# Telemetria.net
KiCad netlist of a schematic drawn in Altium Designer
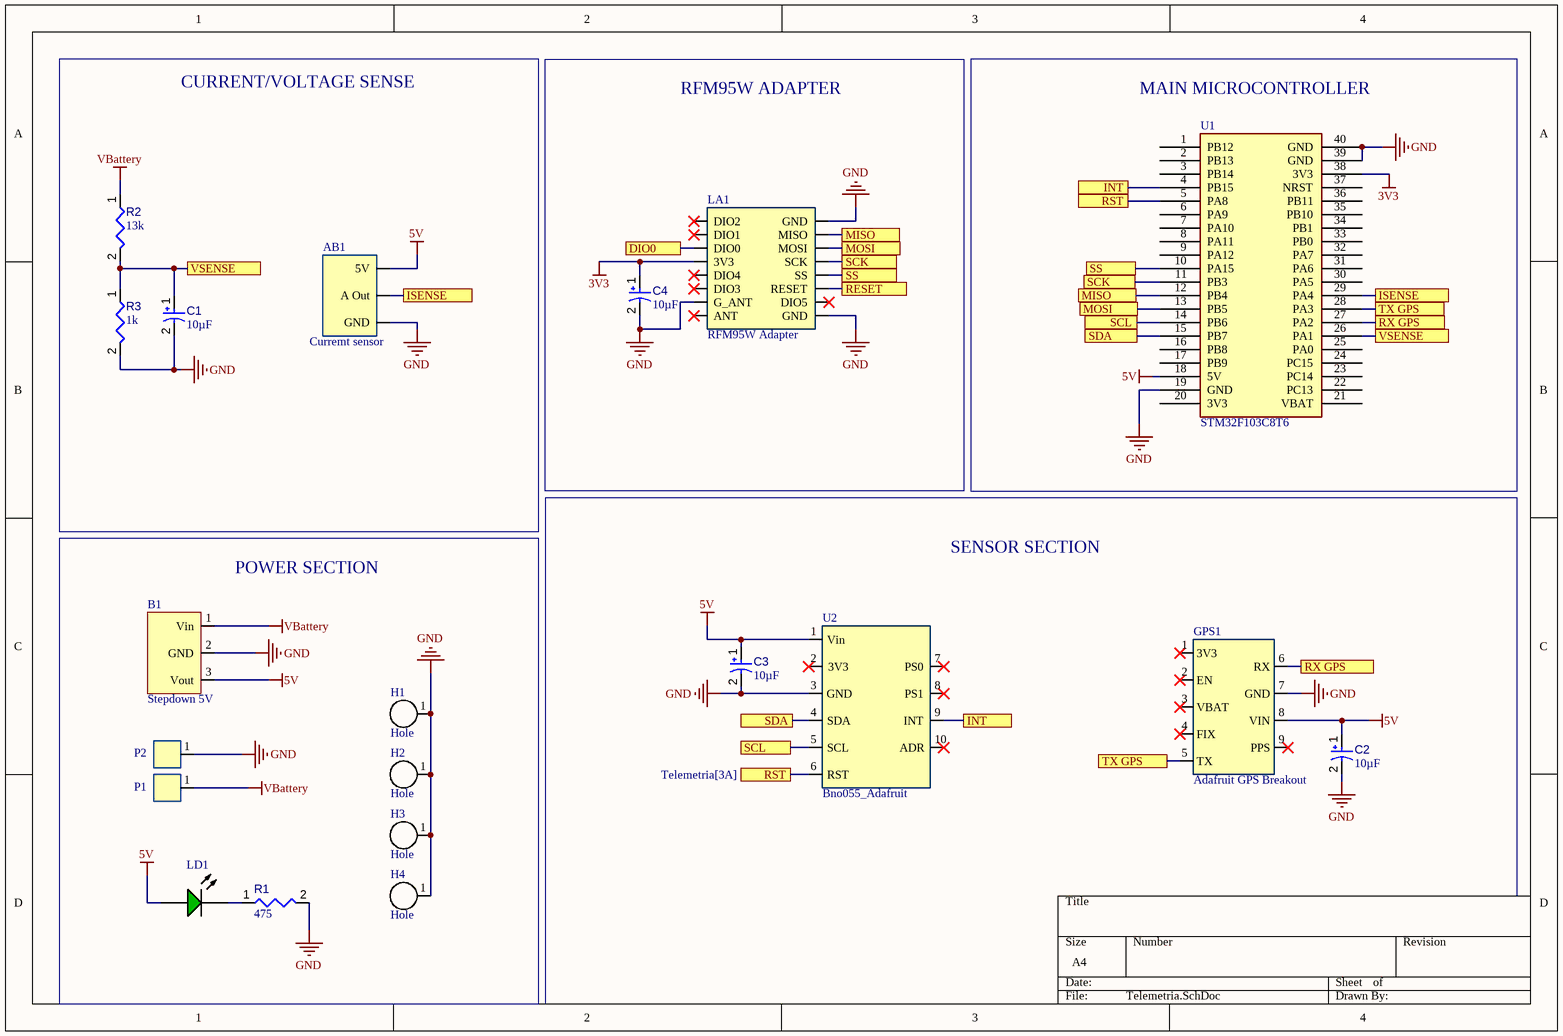
[diagram p0: Telemetria.SchDoc]

(export (version "E")
  (design (tool "Eeschema 10.0.6"))
  (components
    (comp (ref "AB1")
      (value "Curremt sensor")
      (footprint "ACS712 Board")
      (description "ACS712 HAll effect based current sensor")
      (libsource (lib "Bno055_Adafruit") (part "ACS712 Board"))
    )
    (comp (ref "B1")
      (value "Stepdown 5V")
      (footprint "StepDown 5V")
      (description "Buck converter DC-DC 5v Mornsun - K78U05-500R3")
      (libsource (lib "Bno055_Adafruit") (part "Stepdown 5V"))
    )
    (comp (ref "C1")
      (value "10µF")
      (footprint "CAPPR55-200-1100X500X1200")
      (description "Aluminum Electrolytic Capacitor, 10 uF, +/- 20%, 50 V, -40 to 85 degC, 2-Pin THD, RoHS, Bulk")
      (fields (field (name "MANUFACTURER") "Panasonic") (field (name "TOLERANCE") "20%"))
      (libsource (lib "Elyos SEM") (part "CAP-P-2"))
    )
    (comp (ref "C2")
      (value "10µF")
      (footprint "CAPPR55-200-1100X500X1200")
      (description "Aluminum Electrolytic Capacitor, 10 uF, +/- 20%, 50 V, -40 to 85 degC, 2-Pin THD, RoHS, Bulk")
      (fields (field (name "MANUFACTURER") "Panasonic") (field (name "TOLERANCE") "20%"))
      (libsource (lib "Elyos SEM") (part "CAP-P-2"))
    )
    (comp (ref "C3")
      (value "10µF")
      (footprint "CAPPR55-200-1100X500X1200")
      (description "Aluminum Electrolytic Capacitor, 10 uF, +/- 20%, 50 V, -40 to 85 degC, 2-Pin THD, RoHS, Bulk")
      (fields (field (name "MANUFACTURER") "Panasonic") (field (name "TOLERANCE") "20%"))
      (libsource (lib "Elyos SEM") (part "CAP-P-2"))
    )
    (comp (ref "C4")
      (value "10µF")
      (footprint "CAPPR55-200-1100X500X1200")
      (description "Aluminum Electrolytic Capacitor, 10 uF, +/- 20%, 50 V, -40 to 85 degC, 2-Pin THD, RoHS, Bulk")
      (fields (field (name "MANUFACTURER") "Panasonic") (field (name "TOLERANCE") "20%"))
      (libsource (lib "Elyos SEM") (part "CAP-P-2"))
    )
    (comp (ref "GPS1")
      (value "Adafruit GPS Breakout")
      (footprint "Adafruit GPS breakout")
      (description "Adafruit GPS Breakout DIP Board")
      (libsource (lib "Bno055_Adafruit") (part "Adafruit GPS"))
    )
    (comp (ref "H1")
      (value "Hole")
      (footprint "Hole")
      (description "Circular hole for attaching PCB")
      (libsource (lib "Bno055_Adafruit") (part "Hole"))
    )
    (comp (ref "H2")
      (value "Hole")
      (footprint "Hole")
      (description "Circular hole for attaching PCB")
      (libsource (lib "Bno055_Adafruit") (part "Hole"))
    )
    (comp (ref "H3")
      (value "Hole")
      (footprint "Hole")
      (description "Circular hole for attaching PCB")
      (libsource (lib "Bno055_Adafruit") (part "Hole"))
    )
    (comp (ref "H4")
      (value "Hole")
      (footprint "Hole")
      (description "Circular hole for attaching PCB")
      (libsource (lib "Bno055_Adafruit") (part "Hole"))
    )
    (comp (ref "LA1")
      (value "RFM95W Adapter")
      (footprint "Lora Adapter")
      (libsource (lib "Bno055_Adafruit") (part "Lora Adapter"))
    )
    (comp (ref "LD1")
      (value "304090040")
      (footprint "LED-2P-2.28-3MM")
      (description "Green LED, 80 mW, 20 mA, -25 to 85 degC, 2-Pin THD")
      (fields (field (name "MANUFACTURER") "Shenzhen CGX"))
      (libsource (lib "Elyos SEM") (part "LED-GREEN-AK-2"))
    )
    (comp (ref "P1")
      (value "High power pad")
      (footprint "HIGH_POWER_PAD")
      (description "High power pads (7.5 x 15 mm)")
      (libsource (lib "Bno055_Adafruit") (part "HIGH_POWER_PAD"))
    )
    (comp (ref "P2")
      (value "High power pad")
      (footprint "HIGH_POWER_PAD")
      (description "High power pads (7.5 x 15 mm)")
      (libsource (lib "Bno055_Adafruit") (part "HIGH_POWER_PAD"))
    )
    (comp (ref "R1")
      (value "475")
      (footprint "RESA60-630X240")
      (description "Axial Resistor, 475 Ohm, +/- 1%, 0.25 W, -55 to 155 degC, 2-Pin THD, RoHS, Bulk")
      (fields (field (name "MANUFACTURER") "Yageo") (field (name "TOLERANCE") "1%"))
      (libsource (lib "Elyos SEM") (part "RES-2"))
    )
    (comp (ref "R2")
      (value "13k")
      (footprint "RESA60-630X240")
      (description "Axial Resistor, 1 KOhm, +/- 1%, 250 mW, -55 to 155 degC, 2-Pin THD, RoHS, Bulk")
      (fields (field (name "TOLERANCE") "1%") (field (name "POWER") "250mW"))
      (libsource (lib "Elyos SEM") (part "RES-2"))
    )
    (comp (ref "R3")
      (value "1k")
      (footprint "RESA60-630X240")
      (description "Axial Resistor, 1 KOhm, +/- 1%, 250 mW, -55 to 155 degC, 2-Pin THD, RoHS, Bulk")
      (fields (field (name "TOLERANCE") "1%") (field (name "POWER") "250mW"))
      (libsource (lib "Elyos SEM") (part "RES-2"))
    )
    (comp (ref "U1")
      (value "STM32F103C8T6")
      (footprint "Stm32 BluePill")
      (description "Designed By @Alixahedi")
      (libsource (lib "Stm32 Blue Pill") (part "BluePill"))
    )
    (comp (ref "U2")
      (value "Bno055_Adafruit")
      (footprint "Bno055_Adafruit")
      (description "Adafruit IMU breakout part 2472 based on Bosch BNO055 IC")
      (libsource (lib "Bno055_Adafruit") (part "Bno055_Adafruit"))
    )
  )
  (nets
    (net (code "1") (name "/DIO0") (class "Default")
      (node (ref "LA1") (pin "3") (pinfunction "DIO0_3") (pintype "passive"))
    )
    (net (code "2") (name "/INT") (class "Default")
      (node (ref "U1") (pin "4") (pinfunction "PB15_4") (pintype "passive"))
      (node (ref "U2") (pin "9") (pinfunction "INT_9") (pintype "passive"))
    )
    (net (code "3") (name "/ISENSE") (class "Default")
      (node (ref "AB1") (pin "2") (pinfunction "A_Out_2") (pintype "passive"))
      (node (ref "U1") (pin "29") (pinfunction "PA4_29") (pintype "passive"))
    )
    (net (code "4") (name "/MISO") (class "Default")
      (node (ref "LA1") (pin "10") (pinfunction "MISO_10") (pintype "passive"))
      (node (ref "U1") (pin "12") (pinfunction "PB4_12") (pintype "passive"))
    )
    (net (code "5") (name "/MOSI") (class "Default")
      (node (ref "LA1") (pin "11") (pinfunction "MOSI_11") (pintype "passive"))
      (node (ref "U1") (pin "13") (pinfunction "PB5_13") (pintype "passive"))
    )
    (net (code "6") (name "/RESET") (class "Default")
      (node (ref "LA1") (pin "14") (pinfunction "RESET_14") (pintype "passive"))
    )
    (net (code "7") (name "/RST") (class "Default")
      (node (ref "U1") (pin "5") (pinfunction "PA8_5") (pintype "passive"))
      (node (ref "U2") (pin "6") (pinfunction "RST_6") (pintype "passive"))
    )
    (net (code "8") (name "/RX GPS") (class "Default")
      (node (ref "GPS1") (pin "6") (pinfunction "RX_6") (pintype "passive"))
      (node (ref "U1") (pin "27") (pinfunction "PA2_27") (pintype "passive"))
    )
    (net (code "9") (name "/SCK") (class "Default")
      (node (ref "LA1") (pin "12") (pinfunction "SCK_12") (pintype "passive"))
      (node (ref "U1") (pin "11") (pinfunction "PB3_11") (pintype "passive"))
    )
    (net (code "10") (name "/SCL") (class "Default")
      (node (ref "U1") (pin "14") (pinfunction "PB6_14") (pintype "passive"))
      (node (ref "U2") (pin "5") (pinfunction "SCL_5") (pintype "passive"))
    )
    (net (code "11") (name "/SDA") (class "Default")
      (node (ref "U1") (pin "15") (pinfunction "PB7_15") (pintype "passive"))
      (node (ref "U2") (pin "4") (pinfunction "SDA_4") (pintype "passive"))
    )
    (net (code "12") (name "/SS") (class "Default")
      (node (ref "LA1") (pin "13") (pinfunction "SS_13") (pintype "passive"))
      (node (ref "U1") (pin "10") (pinfunction "PA15_10") (pintype "passive"))
    )
    (net (code "13") (name "/TX GPS") (class "Default")
      (node (ref "GPS1") (pin "5") (pinfunction "TX_5") (pintype "passive"))
      (node (ref "U1") (pin "28") (pinfunction "PA3_28") (pintype "passive"))
    )
    (net (code "14") (name "/VSENSE") (class "Default")
      (node (ref "C1") (pin "1") (pinfunction "1_1") (pintype "passive"))
      (node (ref "R2") (pin "2") (pinfunction "2_2") (pintype "passive"))
      (node (ref "R3") (pin "1") (pinfunction "1_1") (pintype "passive"))
      (node (ref "U1") (pin "26") (pinfunction "PA1_26") (pintype "passive"))
    )
    (net (code "15") (name "3V3") (class "Default")
      (node (ref "C4") (pin "1") (pinfunction "1_1") (pintype "passive"))
      (node (ref "LA1") (pin "4") (pinfunction "3V3_4") (pintype "power_in"))
      (node (ref "U1") (pin "38") (pinfunction "3V3_38") (pintype "passive"))
    )
    (net (code "16") (name "5V") (class "Default")
      (node (ref "AB1") (pin "3") (pinfunction "5V_3") (pintype "passive"))
      (node (ref "B1") (pin "3") (pinfunction "Vout_3") (pintype "passive"))
      (node (ref "C2") (pin "1") (pinfunction "1_1") (pintype "passive"))
      (node (ref "C3") (pin "1") (pinfunction "1_1") (pintype "passive"))
      (node (ref "GPS1") (pin "8") (pinfunction "VIN_8") (pintype "passive"))
      (node (ref "LD1") (pin "1") (pinfunction "A_1") (pintype "passive"))
      (node (ref "U1") (pin "18") (pinfunction "5V_18") (pintype "passive"))
      (node (ref "U2") (pin "1") (pinfunction "__Vin_1") (pintype "passive"))
    )
    (net (code "17") (name "GND") (class "Default")
      (node (ref "AB1") (pin "1") (pinfunction "GND_1") (pintype "passive"))
      (node (ref "B1") (pin "2") (pinfunction "GND_2") (pintype "passive"))
      (node (ref "C1") (pin "2") (pinfunction "2_2") (pintype "passive"))
      (node (ref "C2") (pin "2") (pinfunction "2_2") (pintype "passive"))
      (node (ref "C3") (pin "2") (pinfunction "2_2") (pintype "passive"))
      (node (ref "C4") (pin "2") (pinfunction "2_2") (pintype "passive"))
      (node (ref "GPS1") (pin "7") (pinfunction "GND_7") (pintype "passive"))
      (node (ref "H1") (pin "1") (pinfunction "GND_1") (pintype "passive"))
      (node (ref "H2") (pin "1") (pinfunction "GND_1") (pintype "passive"))
      (node (ref "H3") (pin "1") (pinfunction "GND_1") (pintype "passive"))
      (node (ref "H4") (pin "1") (pinfunction "GND_1") (pintype "passive"))
      (node (ref "LA1") (pin "16") (pinfunction "GND_16") (pintype "passive"))
      (node (ref "LA1") (pin "7") (pinfunction "G_ANT_7") (pintype "passive"))
      (node (ref "LA1") (pin "9") (pinfunction "GND_9") (pintype "passive"))
      (node (ref "P2") (pin "1") (pinfunction "PAD_1") (pintype "passive"))
      (node (ref "R1") (pin "2") (pinfunction "2_2") (pintype "passive"))
      (node (ref "R3") (pin "2") (pinfunction "2_2") (pintype "passive"))
      (node (ref "U1") (pin "19") (pinfunction "GND_19") (pintype "passive"))
      (node (ref "U1") (pin "39") (pinfunction "GND_39") (pintype "passive"))
      (node (ref "U1") (pin "40") (pinfunction "GND_40") (pintype "passive"))
      (node (ref "U2") (pin "3") (pinfunction "GND_3") (pintype "passive"))
    )
    (net (code "18") (name "Net-(LD1-K)") (class "Default")
      (node (ref "LD1") (pin "2") (pinfunction "K_2") (pintype "passive"))
      (node (ref "R1") (pin "1") (pinfunction "1_1") (pintype "passive"))
    )
    (net (code "19") (name "VBattery") (class "Default")
      (node (ref "B1") (pin "1") (pinfunction "Vin_1") (pintype "passive"))
      (node (ref "P1") (pin "1") (pinfunction "PAD_1") (pintype "passive"))
      (node (ref "R2") (pin "1") (pinfunction "1_1") (pintype "passive"))
    )
    (net (code "20") (name "unconnected-(GPS1-3V3-Pad1)") (class "Default")
      (node (ref "GPS1") (pin "1") (pinfunction "3V3_1") (pintype "passive+no_connect"))
    )
    (net (code "21") (name "unconnected-(GPS1-EN-Pad2)") (class "Default")
      (node (ref "GPS1") (pin "2") (pinfunction "EN_2") (pintype "passive+no_connect"))
    )
    (net (code "22") (name "unconnected-(GPS1-FIX-Pad4)") (class "Default")
      (node (ref "GPS1") (pin "4") (pinfunction "FIX_4") (pintype "passive+no_connect"))
    )
    (net (code "23") (name "unconnected-(GPS1-PPS-Pad9)") (class "Default")
      (node (ref "GPS1") (pin "9") (pinfunction "PPS_9") (pintype "passive+no_connect"))
    )
    (net (code "24") (name "unconnected-(GPS1-VBAT-Pad3)") (class "Default")
      (node (ref "GPS1") (pin "3") (pinfunction "VBAT_3") (pintype "passive+no_connect"))
    )
    (net (code "25") (name "unconnected-(LA1-ANT-Pad8)") (class "Default")
      (node (ref "LA1") (pin "8") (pinfunction "ANT_8") (pintype "passive+no_connect"))
    )
    (net (code "26") (name "unconnected-(LA1-DIO1-Pad2)") (class "Default")
      (node (ref "LA1") (pin "2") (pinfunction "DIO1_2") (pintype "passive+no_connect"))
    )
    (net (code "27") (name "unconnected-(LA1-DIO2-Pad1)") (class "Default")
      (node (ref "LA1") (pin "1") (pinfunction "DIO2_1") (pintype "passive+no_connect"))
    )
    (net (code "28") (name "unconnected-(LA1-DIO3-Pad6)") (class "Default")
      (node (ref "LA1") (pin "6") (pinfunction "DIO3_6") (pintype "passive+no_connect"))
    )
    (net (code "29") (name "unconnected-(LA1-DIO4-Pad5)") (class "Default")
      (node (ref "LA1") (pin "5") (pinfunction "DIO4_5") (pintype "passive+no_connect"))
    )
    (net (code "30") (name "unconnected-(LA1-DIO5-Pad15)") (class "Default")
      (node (ref "LA1") (pin "15") (pinfunction "DIO5_15") (pintype "passive+no_connect"))
    )
    (net (code "31") (name "unconnected-(U1-3V3-Pad20)") (class "Default")
      (node (ref "U1") (pin "20") (pinfunction "3V3_20") (pintype "passive"))
    )
    (net (code "32") (name "unconnected-(U1-NRST-Pad37)") (class "Default")
      (node (ref "U1") (pin "37") (pinfunction "NRST_37") (pintype "passive"))
    )
    (net (code "33") (name "unconnected-(U1-PA0-Pad25)") (class "Default")
      (node (ref "U1") (pin "25") (pinfunction "PA0_25") (pintype "passive"))
    )
    (net (code "34") (name "unconnected-(U1-PA5-Pad30)") (class "Default")
      (node (ref "U1") (pin "30") (pinfunction "PA5_30") (pintype "passive"))
    )
    (net (code "35") (name "unconnected-(U1-PA6-Pad31)") (class "Default")
      (node (ref "U1") (pin "31") (pinfunction "PA6_31") (pintype "passive"))
    )
    (net (code "36") (name "unconnected-(U1-PA7-Pad32)") (class "Default")
      (node (ref "U1") (pin "32") (pinfunction "PA7_32") (pintype "passive"))
    )
    (net (code "37") (name "unconnected-(U1-PA9-Pad6)") (class "Default")
      (node (ref "U1") (pin "6") (pinfunction "PA9_6") (pintype "passive"))
    )
    (net (code "38") (name "unconnected-(U1-PA10-Pad7)") (class "Default")
      (node (ref "U1") (pin "7") (pinfunction "PA10_7") (pintype "passive"))
    )
    (net (code "39") (name "unconnected-(U1-PA11-Pad8)") (class "Default")
      (node (ref "U1") (pin "8") (pinfunction "PA11_8") (pintype "passive"))
    )
    (net (code "40") (name "unconnected-(U1-PA12-Pad9)") (class "Default")
      (node (ref "U1") (pin "9") (pinfunction "PA12_9") (pintype "passive"))
    )
    (net (code "41") (name "unconnected-(U1-PB0-Pad33)") (class "Default")
      (node (ref "U1") (pin "33") (pinfunction "PB0_33") (pintype "passive"))
    )
    (net (code "42") (name "unconnected-(U1-PB1-Pad34)") (class "Default")
      (node (ref "U1") (pin "34") (pinfunction "PB1_34") (pintype "passive"))
    )
    (net (code "43") (name "unconnected-(U1-PB8-Pad16)") (class "Default")
      (node (ref "U1") (pin "16") (pinfunction "PB8_16") (pintype "passive"))
    )
    (net (code "44") (name "unconnected-(U1-PB9-Pad17)") (class "Default")
      (node (ref "U1") (pin "17") (pinfunction "PB9_17") (pintype "passive"))
    )
    (net (code "45") (name "unconnected-(U1-PB10-Pad35)") (class "Default")
      (node (ref "U1") (pin "35") (pinfunction "PB10_35") (pintype "passive"))
    )
    (net (code "46") (name "unconnected-(U1-PB11-Pad36)") (class "Default")
      (node (ref "U1") (pin "36") (pinfunction "PB11_36") (pintype "passive"))
    )
    (net (code "47") (name "unconnected-(U1-PB12-Pad1)") (class "Default")
      (node (ref "U1") (pin "1") (pinfunction "PB12_1") (pintype "passive"))
    )
    (net (code "48") (name "unconnected-(U1-PB13-Pad2)") (class "Default")
      (node (ref "U1") (pin "2") (pinfunction "PB13_2") (pintype "passive"))
    )
    (net (code "49") (name "unconnected-(U1-PB14-Pad3)") (class "Default")
      (node (ref "U1") (pin "3") (pinfunction "PB14_3") (pintype "passive"))
    )
    (net (code "50") (name "unconnected-(U1-PC13-Pad22)") (class "Default")
      (node (ref "U1") (pin "22") (pinfunction "PC13_22") (pintype "passive"))
    )
    (net (code "51") (name "unconnected-(U1-PC14-Pad23)") (class "Default")
      (node (ref "U1") (pin "23") (pinfunction "PC14_23") (pintype "passive"))
    )
    (net (code "52") (name "unconnected-(U1-PC15-Pad24)") (class "Default")
      (node (ref "U1") (pin "24") (pinfunction "PC15_24") (pintype "passive"))
    )
    (net (code "53") (name "unconnected-(U1-VBAT-Pad21)") (class "Default")
      (node (ref "U1") (pin "21") (pinfunction "VBAT_21") (pintype "passive"))
    )
    (net (code "54") (name "unconnected-(U2-3V3-Pad2)") (class "Default")
      (node (ref "U2") (pin "2") (pinfunction "3V3_2") (pintype "passive+no_connect"))
    )
    (net (code "55") (name "unconnected-(U2-ADR-Pad10)") (class "Default")
      (node (ref "U2") (pin "10") (pinfunction "ADR_10") (pintype "passive+no_connect"))
    )
    (net (code "56") (name "unconnected-(U2-PS0-Pad7)") (class "Default")
      (node (ref "U2") (pin "7") (pinfunction "PS0_7") (pintype "passive+no_connect"))
    )
    (net (code "57") (name "unconnected-(U2-PS1-Pad8)") (class "Default")
      (node (ref "U2") (pin "8") (pinfunction "PS1_8") (pintype "passive+no_connect"))
    )
  )
)
